# OSP_Carrier_V8_FM-ExG.net
KiCad netlist of a schematic drawn in Altium Designer
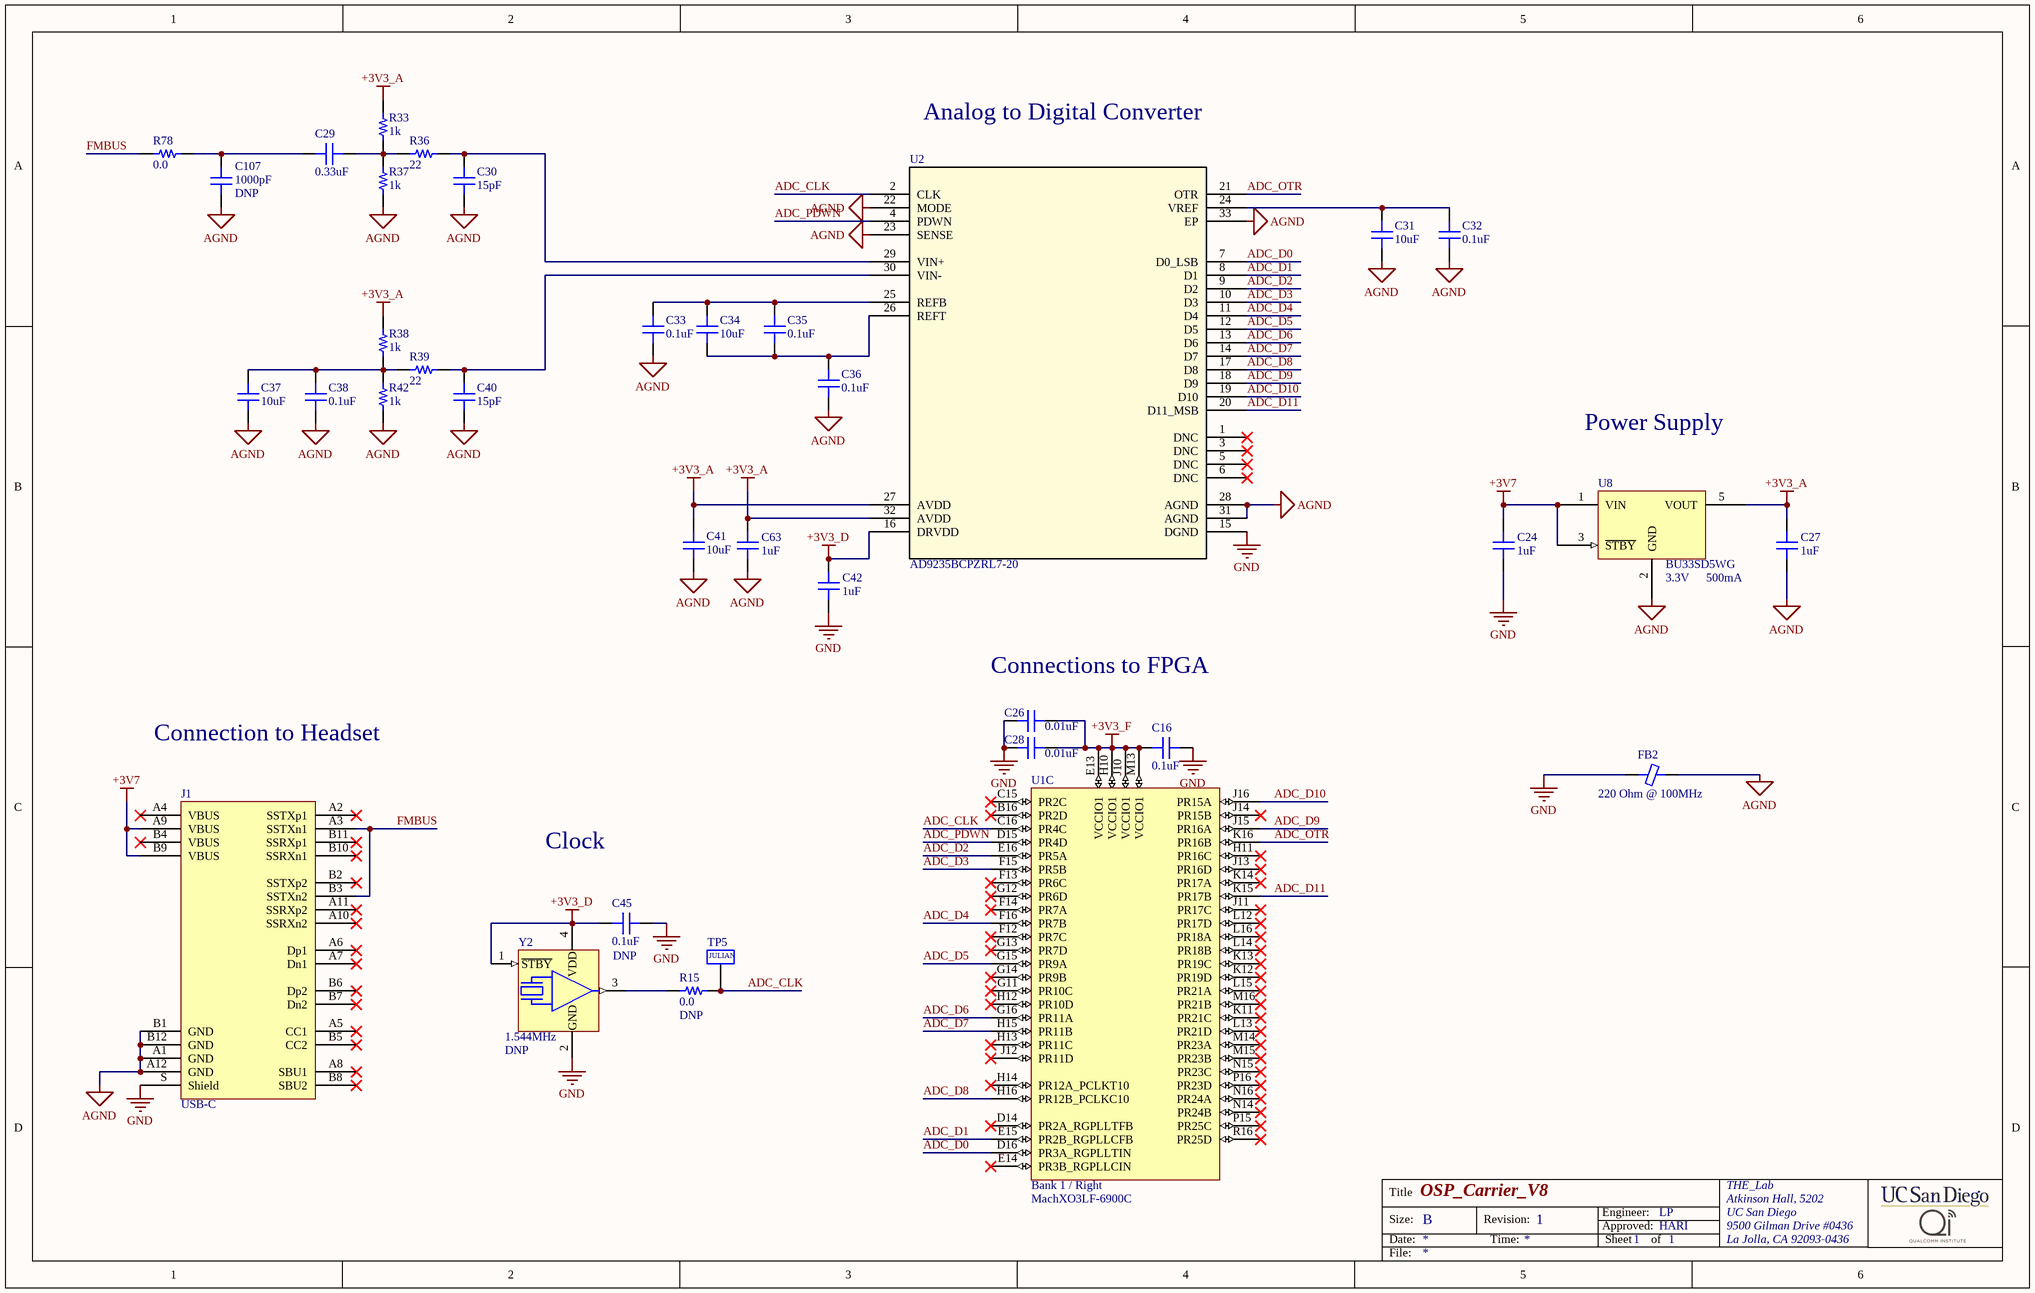
[diagram p0: OSP_Carrier_V8_FM-ExG.SchDoc]

(export (version "E")
  (design (tool "Eeschema 10.0.6"))
  (components
    (comp (ref "C16")
      (value "0.1uF")
      (footprint "CAP 0402/1005")
      (description "CAP CER 0.1UF 50V X7R 0402")
      (fields
        (field (name "PART NUMBER") "C1005X7R1H104K050BB")
        (field (name "MANUFACTURER") "TDK Corporation")
      )
      (libsource (lib "Celestial Library Database") (part "Capacitor"))
    )
    (comp (ref "C24")
      (value "1uF")
      (footprint "CAP 0402/1005")
      (description "CAP CER 1UF 10V X5R 0402")
      (fields
        (field (name "PART NUMBER") "GRM155R61A105KE15D")
        (field (name "MANUFACTURER") "Murata Electronics North America")
      )
      (libsource (lib "Celestial Library Database") (part "Capacitor"))
    )
    (comp (ref "C26")
      (value "0.01uF")
      (footprint "CAP 0402/1005")
      (description "CAP CER 10000PF 25V X7R 0402")
      (fields (field (name "PART NUMBER") "CC0402KRX7R8BB103") (field (name "MANUFACTURER") "Yageo"))
      (libsource (lib "Celestial Library Database") (part "Capacitor"))
    )
    (comp (ref "C27")
      (value "1uF")
      (footprint "CAP 0402/1005")
      (description "CAP CER 1UF 10V X5R 0402")
      (fields
        (field (name "PART NUMBER") "GRM155R61A105KE15D")
        (field (name "MANUFACTURER") "Murata Electronics North America")
      )
      (libsource (lib "Celestial Library Database") (part "Capacitor"))
    )
    (comp (ref "C28")
      (value "0.01uF")
      (footprint "CAP 0402/1005")
      (description "CAP CER 10000PF 25V X7R 0402")
      (fields (field (name "PART NUMBER") "CC0402KRX7R8BB103") (field (name "MANUFACTURER") "Yageo"))
      (libsource (lib "Celestial Library Database") (part "Capacitor"))
    )
    (comp (ref "C29")
      (value "0.33uF")
      (footprint "CAP 0402/1005")
      (description "CAP CER 1UF 10V X5R 0402")
      (fields
        (field (name "PART NUMBER") "GRM155R61A105KE15D")
        (field (name "MANUFACTURER") "Murata Electronics North America")
      )
      (libsource (lib "Celestial Library Database") (part "Capacitor"))
    )
    (comp (ref "C30")
      (value "15pF")
      (footprint "CAP 0402/1005")
      (description "CAP CER 15PF 50V C0G 0402")
      (fields
        (field (name "PART NUMBER") "C1005C0G1H150F050BA")
        (field (name "MANUFACTURER") "TDK Corporation")
      )
      (libsource (lib "Celestial Library Database") (part "Capacitor"))
    )
    (comp (ref "C31")
      (value "10uF")
      (footprint "CAP 0805/2012")
      (description "CAP CER 10UF 10V X5R 0805")
      (fields
        (field (name "PART NUMBER") "C2012X5R1A106M125AB")
        (field (name "MANUFACTURER") "TDK Corporation")
      )
      (libsource (lib "Celestial Library Database") (part "Capacitor"))
    )
    (comp (ref "C32")
      (value "0.1uF")
      (footprint "CAP 0402/1005")
      (description "CAP CER 0.1UF 50V X7R 0402")
      (fields
        (field (name "PART NUMBER") "C1005X7R1H104K050BB")
        (field (name "MANUFACTURER") "TDK Corporation")
      )
      (libsource (lib "Celestial Library Database") (part "Capacitor"))
    )
    (comp (ref "C33")
      (value "0.1uF")
      (footprint "CAP 0402/1005")
      (description "CAP CER 0.1UF 50V X7R 0402")
      (fields
        (field (name "PART NUMBER") "C1005X7R1H104K050BB")
        (field (name "MANUFACTURER") "TDK Corporation")
      )
      (libsource (lib "Celestial Library Database") (part "Capacitor"))
    )
    (comp (ref "C34")
      (value "10uF")
      (footprint "CAP 0805/2012")
      (description "CAP CER 10UF 10V X5R 0805")
      (fields
        (field (name "PART NUMBER") "C2012X5R1A106M125AB")
        (field (name "MANUFACTURER") "TDK Corporation")
      )
      (libsource (lib "Celestial Library Database") (part "Capacitor"))
    )
    (comp (ref "C35")
      (value "0.1uF")
      (footprint "CAP 0402/1005")
      (description "CAP CER 0.1UF 50V X7R 0402")
      (fields
        (field (name "PART NUMBER") "C1005X7R1H104K050BB")
        (field (name "MANUFACTURER") "TDK Corporation")
      )
      (libsource (lib "Celestial Library Database") (part "Capacitor"))
    )
    (comp (ref "C36")
      (value "0.1uF")
      (footprint "CAP 0402/1005")
      (description "CAP CER 0.1UF 50V X7R 0402")
      (fields
        (field (name "PART NUMBER") "C1005X7R1H104K050BB")
        (field (name "MANUFACTURER") "TDK Corporation")
      )
      (libsource (lib "Celestial Library Database") (part "Capacitor"))
    )
    (comp (ref "C37")
      (value "10uF")
      (footprint "CAP 0805/2012")
      (description "CAP CER 10UF 10V X5R 0805")
      (fields
        (field (name "PART NUMBER") "C2012X5R1A106M125AB")
        (field (name "MANUFACTURER") "TDK Corporation")
      )
      (libsource (lib "Celestial Library Database") (part "Capacitor"))
    )
    (comp (ref "C38")
      (value "0.1uF")
      (footprint "CAP 0402/1005")
      (description "CAP CER 0.1UF 50V X7R 0402")
      (fields
        (field (name "PART NUMBER") "C1005X7R1H104K050BB")
        (field (name "MANUFACTURER") "TDK Corporation")
      )
      (libsource (lib "Celestial Library Database") (part "Capacitor"))
    )
    (comp (ref "C40")
      (value "15pF")
      (footprint "CAP 0402/1005")
      (description "CAP CER 15PF 50V C0G 0402")
      (fields
        (field (name "PART NUMBER") "C1005C0G1H150F050BA")
        (field (name "MANUFACTURER") "TDK Corporation")
      )
      (libsource (lib "Celestial Library Database") (part "Capacitor"))
    )
    (comp (ref "C41")
      (value "10uF")
      (footprint "CAP 0805/2012")
      (description "CAP CER 10UF 10V X5R 0805")
      (fields
        (field (name "PART NUMBER") "C2012X5R1A106M125AB")
        (field (name "MANUFACTURER") "TDK Corporation")
      )
      (libsource (lib "Celestial Library Database") (part "Capacitor"))
    )
    (comp (ref "C42")
      (value "1uF")
      (footprint "CAP 0402/1005")
      (description "CAP CER 1UF 10V X5R 0402")
      (fields
        (field (name "PART NUMBER") "GRM155R61A105KE15D")
        (field (name "MANUFACTURER") "Murata Electronics North America")
      )
      (libsource (lib "Celestial Library Database") (part "Capacitor"))
    )
    (comp (ref "C45")
      (value "0.1uF")
      (footprint "CAP 0402/1005")
      (description "CAP CER 0.1UF 50V X7R 0402")
      (fields
        (field (name "PART NUMBER") "C1005X7R1H104K050BB")
        (field (name "MANUFACTURER") "TDK Corporation")
        (field (name "DNP") "DNP")
      )
      (libsource (lib "Celestial Library Database") (part "Capacitor"))
    )
    (comp (ref "C63")
      (value "1uF")
      (footprint "CAP 0402/1005")
      (description "CAP CER 1UF 10V X5R 0402")
      (fields
        (field (name "PART NUMBER") "GRM155R61A105KE15D")
        (field (name "MANUFACTURER") "Murata Electronics North America")
      )
      (libsource (lib "Celestial Library Database") (part "Capacitor"))
    )
    (comp (ref "C107")
      (value "1000pF")
      (footprint "CAP 0805/2012")
      (description "CAP CER 1000PF 50V C0G 0805")
      (fields
        (field (name "PART NUMBER") "C2012C0G1H102J060AA")
        (field (name "MANUFACTURER") "TDK Corporation")
        (field (name "DNP") "DNP")
      )
      (libsource (lib "Celestial Library Database") (part "Capacitor"))
    )
    (comp (ref "FB2")
      (value "220 Ohm @ 100MHz")
      (footprint "FER 0402/1005")
      (description "FERRITE CHIP 220 OHM 500MA 0402")
      (fields
        (field (name "PART NUMBER") "CIM05U221NC")
        (field (name "MANUFACTURER") "Samsung Electro-Mechanics America, Inc.")
      )
      (libsource (lib "Celestial Library Database") (part "Ferrite Chip"))
    )
    (comp (ref "J1")
      (value "USB-C")
      (footprint "TE_USB-C_2129691-1")
      (description "TE 2129691-1 USB-C Socket")
      (libsource (lib "OSP_Symbols") (part "TE_USB_C_2129691-1"))
    )
    (comp (ref "R15")
      (value "0.0")
      (footprint "RES 0603/1608")
      (description "RES SMD 0.0 OHM JUMPER 1/4W 0603")
      (fields
        (field (name "PART NUMBER") "CRCW06030000Z0EAHP")
        (field (name "MANUFACTURER") "Vishay Dale")
        (field (name "DNP") "DNP")
      )
      (libsource (lib "Celestial Library Database") (part "Resistor"))
    )
    (comp (ref "R33")
      (value "1k")
      (footprint "RES 0402/1005")
      (description "RES SMD 1K OHM 1% 1/10W 0402")
      (fields
        (field (name "PART NUMBER") "ERJ-2RKF1001X")
        (field (name "MANUFACTURER") "Panasonic Electronic Components")
      )
      (libsource (lib "Celestial Library Database") (part "Resistor"))
    )
    (comp (ref "R36")
      (value "22")
      (footprint "RES 0402/1005")
      (description "RES SMD 22 OHM 1% 1/10W 0402")
      (fields
        (field (name "PART NUMBER") "ERJ-2RKF22R0X")
        (field (name "MANUFACTURER") "Panasonic Electronic Components")
      )
      (libsource (lib "Celestial Library Database") (part "Resistor"))
    )
    (comp (ref "R37")
      (value "1k")
      (footprint "RES 0402/1005")
      (description "RES SMD 1K OHM 1% 1/10W 0402")
      (fields
        (field (name "PART NUMBER") "ERJ-2RKF1001X")
        (field (name "MANUFACTURER") "Panasonic Electronic Components")
      )
      (libsource (lib "Celestial Library Database") (part "Resistor"))
    )
    (comp (ref "R38")
      (value "1k")
      (footprint "RES 0402/1005")
      (description "RES SMD 1K OHM 1% 1/10W 0402")
      (fields
        (field (name "PART NUMBER") "ERJ-2RKF1001X")
        (field (name "MANUFACTURER") "Panasonic Electronic Components")
      )
      (libsource (lib "Celestial Library Database") (part "Resistor"))
    )
    (comp (ref "R39")
      (value "22")
      (footprint "RES 0402/1005")
      (description "RES SMD 22 OHM 1% 1/10W 0402")
      (fields
        (field (name "PART NUMBER") "ERJ-2RKF22R0X")
        (field (name "MANUFACTURER") "Panasonic Electronic Components")
      )
      (libsource (lib "Celestial Library Database") (part "Resistor"))
    )
    (comp (ref "R42")
      (value "1k")
      (footprint "RES 0402/1005")
      (description "RES SMD 1K OHM 1% 1/10W 0402")
      (fields
        (field (name "PART NUMBER") "ERJ-2RKF1001X")
        (field (name "MANUFACTURER") "Panasonic Electronic Components")
      )
      (libsource (lib "Celestial Library Database") (part "Resistor"))
    )
    (comp (ref "R78")
      (value "0.0")
      (footprint "RES 0805/2012")
      (description "RES SMD 0.0 OHM JUMPER 1/2W 0805")
      (fields (field (name "PART NUMBER") "CRCW08050000Z0EAHP") (field (name "MANUFACTURER") "Vishay Dale"))
      (libsource (lib "Celestial Library Database") (part "Resistor"))
    )
    (comp (ref "TP5")
      (value "TP_SMD_JULIAN")
      (footprint "TP_SMD_JULIAN")
      (description "Julian Extra-Large SMD Test Point")
      (libsource (lib "OSP_Symbols") (part "TP_SMD_JULIAN"))
    )
    (comp (ref "U1")
      (value "MachXO3LF-6900C")
      (footprint "LCMXO3_caBGA_BG256")
      (description "Lattice MachXO3LF-6900C-5BG256C FPGA")
      (libsource (lib "OSP_Symbols") (part "LCMXO3LF-6900C-XBG256X"))
    )
    (comp (ref "U2")
      (value "AD9235BCPZRL7-20")
      (footprint "CP_32_2-M")
      (description "Imported")
      (libsource (lib "AD9235BCPZRL7-20") (part "AD9235BCPZRL7-20"))
    )
    (comp (ref "U8")
      (value "BU33SD5WG")
      (footprint "ROHM_SSOP5")
      (description "ROHM BU33SD5WG-TR 3.3V 500mA LDO")
      (fields (field (name "VOLTAGE") "3.3V") (field (name "CURRENT") "500mA"))
      (libsource (lib "OSP_Symbols") (part "ROHM_BU33SD5WG"))
    )
    (comp (ref "Y2")
      (value "1.544MHz")
      (footprint "ABRACON_ASFLMB")
      (description "Abracon ASFLMB-1.544MHZ-LR-T")
      (fields (field (name "DNP") "DNP"))
      (libsource (lib "OSP_Symbols") (part "ABRA_ASFLMB-1.544MHZ-LR-T"))
    )
  )
  (nets
    (net (code "1") (name "+3V3_A") (class "Default")
      (node (ref "C27") (pin "1") (pinfunction "1_1") (pintype "passive"))
      (node (ref "C41") (pin "2") (pinfunction "2_2") (pintype "passive"))
      (node (ref "C63") (pin "1") (pinfunction "1_1") (pintype "passive"))
      (node (ref "R33") (pin "2") (pinfunction "2_2") (pintype "passive"))
      (node (ref "R38") (pin "2") (pinfunction "2_2") (pintype "passive"))
      (node (ref "U2") (pin "27") (pinfunction "AVDD_27") (pintype "power_in"))
      (node (ref "U2") (pin "32") (pinfunction "AVDD_32") (pintype "power_in"))
      (node (ref "U8") (pin "5") (pinfunction "VOUT_5") (pintype "power_in"))
    )
    (net (code "2") (name "+3V3_D") (class "Default")
      (node (ref "C42") (pin "1") (pinfunction "1_1") (pintype "passive"))
      (node (ref "C45") (pin "2") (pinfunction "2_2") (pintype "passive"))
      (node (ref "U2") (pin "16") (pinfunction "DRVDD_16") (pintype "power_in"))
      (node (ref "Y2") (pin "1") (pinfunction "~{STBY}_1") (pintype "input"))
      (node (ref "Y2") (pin "4") (pinfunction "VDD_4") (pintype "power_in"))
    )
    (net (code "3") (name "+3V3_F") (class "Default")
      (node (ref "C16") (pin "2") (pinfunction "2_2") (pintype "passive"))
      (node (ref "C26") (pin "1") (pinfunction "1_1") (pintype "passive"))
      (node (ref "C28") (pin "1") (pinfunction "1_1") (pintype "passive"))
      (node (ref "U1") (pin "E13") (pinfunction "VCCIO1_E13") (pintype "bidirectional"))
      (node (ref "U1") (pin "H10") (pinfunction "VCCIO1_H10") (pintype "bidirectional"))
      (node (ref "U1") (pin "J10") (pinfunction "VCCIO1_J10") (pintype "bidirectional"))
      (node (ref "U1") (pin "M13") (pinfunction "VCCIO1_M13") (pintype "bidirectional"))
    )
    (net (code "4") (name "+3V7") (class "Default")
      (node (ref "C24") (pin "1") (pinfunction "1_1") (pintype "passive"))
      (node (ref "J1") (pin "A9") (pinfunction "VBUS_A9") (pintype "passive"))
      (node (ref "J1") (pin "B9") (pinfunction "VBUS_B9") (pintype "passive"))
      (node (ref "U8") (pin "1") (pinfunction "VIN_1") (pintype "power_in"))
      (node (ref "U8") (pin "3") (pinfunction "~{STBY}_3") (pintype "input"))
    )
    (net (code "5") (name "/ADC_CLK") (class "Default")
      (node (ref "R15") (pin "1") (pinfunction "1_1") (pintype "passive"))
      (node (ref "TP5") (pin "1") (pintype "passive"))
      (node (ref "U1") (pin "C16") (pinfunction "PR4C_C16") (pintype "bidirectional"))
      (node (ref "U2") (pin "2") (pinfunction "CLK_2") (pintype "passive"))
    )
    (net (code "6") (name "/ADC_D0") (class "Default")
      (node (ref "U1") (pin "D16") (pinfunction "PR3A_RGPLLTIN_D16") (pintype "bidirectional"))
      (node (ref "U2") (pin "7") (pinfunction "D0_LSB_7") (pintype "passive"))
    )
    (net (code "7") (name "/ADC_D1") (class "Default")
      (node (ref "U1") (pin "E15") (pinfunction "PR2B_RGPLLCFB_E15") (pintype "bidirectional"))
      (node (ref "U2") (pin "8") (pinfunction "D1_8") (pintype "passive"))
    )
    (net (code "8") (name "/ADC_D2") (class "Default")
      (node (ref "U1") (pin "E16") (pinfunction "PR5A_E16") (pintype "bidirectional"))
      (node (ref "U2") (pin "9") (pinfunction "D2_9") (pintype "passive"))
    )
    (net (code "9") (name "/ADC_D3") (class "Default")
      (node (ref "U1") (pin "F15") (pinfunction "PR5B_F15") (pintype "bidirectional"))
      (node (ref "U2") (pin "10") (pinfunction "D3_10") (pintype "passive"))
    )
    (net (code "10") (name "/ADC_D4") (class "Default")
      (node (ref "U1") (pin "F16") (pinfunction "PR7B_F16") (pintype "bidirectional"))
      (node (ref "U2") (pin "11") (pinfunction "D4_11") (pintype "passive"))
    )
    (net (code "11") (name "/ADC_D5") (class "Default")
      (node (ref "U1") (pin "G15") (pinfunction "PR9A_G15") (pintype "bidirectional"))
      (node (ref "U2") (pin "12") (pinfunction "D5_12") (pintype "passive"))
    )
    (net (code "12") (name "/ADC_D6") (class "Default")
      (node (ref "U1") (pin "G16") (pinfunction "PR11A_G16") (pintype "bidirectional"))
      (node (ref "U2") (pin "13") (pinfunction "D6_13") (pintype "passive"))
    )
    (net (code "13") (name "/ADC_D7") (class "Default")
      (node (ref "U1") (pin "H15") (pinfunction "PR11B_H15") (pintype "bidirectional"))
      (node (ref "U2") (pin "14") (pinfunction "D7_14") (pintype "passive"))
    )
    (net (code "14") (name "/ADC_D8") (class "Default")
      (node (ref "U1") (pin "H16") (pinfunction "PR12B_PCLKC10_H16") (pintype "bidirectional"))
      (node (ref "U2") (pin "17") (pinfunction "D8_17") (pintype "passive"))
    )
    (net (code "15") (name "/ADC_D9") (class "Default")
      (node (ref "U1") (pin "J15") (pinfunction "PR16A_J15") (pintype "bidirectional"))
      (node (ref "U2") (pin "18") (pinfunction "D9_18") (pintype "passive"))
    )
    (net (code "16") (name "/ADC_D10") (class "Default")
      (node (ref "U1") (pin "J16") (pinfunction "PR15A_J16") (pintype "bidirectional"))
      (node (ref "U2") (pin "19") (pinfunction "D10_19") (pintype "passive"))
    )
    (net (code "17") (name "/ADC_D11") (class "Default")
      (node (ref "U1") (pin "K15") (pinfunction "PR17B_K15") (pintype "bidirectional"))
      (node (ref "U2") (pin "20") (pinfunction "D11_MSB_20") (pintype "passive"))
    )
    (net (code "18") (name "/ADC_OTR") (class "Default")
      (node (ref "U1") (pin "K16") (pinfunction "PR16B_K16") (pintype "bidirectional"))
      (node (ref "U2") (pin "21") (pinfunction "OTR_21") (pintype "passive"))
    )
    (net (code "19") (name "/ADC_PDWN") (class "Default")
      (node (ref "U1") (pin "D15") (pinfunction "PR4D_D15") (pintype "bidirectional"))
      (node (ref "U2") (pin "4") (pinfunction "PDWN_4") (pintype "passive"))
    )
    (net (code "20") (name "/FMBUS") (class "Default")
      (node (ref "J1") (pin "A3") (pinfunction "SSTXn1_A3") (pintype "passive"))
      (node (ref "J1") (pin "B3") (pinfunction "SSTXn2_B3") (pintype "passive"))
      (node (ref "R78") (pin "1") (pinfunction "1_1") (pintype "passive"))
    )
    (net (code "21") (name "AGND") (class "Default")
      (node (ref "C107") (pin "1") (pinfunction "1_1") (pintype "passive"))
      (node (ref "C27") (pin "2") (pinfunction "2_2") (pintype "passive"))
      (node (ref "C30") (pin "1") (pinfunction "1_1") (pintype "passive"))
      (node (ref "C31") (pin "1") (pinfunction "1_1") (pintype "passive"))
      (node (ref "C32") (pin "2") (pinfunction "2_2") (pintype "passive"))
      (node (ref "C33") (pin "2") (pinfunction "2_2") (pintype "passive"))
      (node (ref "C36") (pin "2") (pinfunction "2_2") (pintype "passive"))
      (node (ref "C37") (pin "1") (pinfunction "1_1") (pintype "passive"))
      (node (ref "C38") (pin "2") (pinfunction "2_2") (pintype "passive"))
      (node (ref "C40") (pin "1") (pinfunction "1_1") (pintype "passive"))
      (node (ref "C41") (pin "1") (pinfunction "1_1") (pintype "passive"))
      (node (ref "C63") (pin "2") (pinfunction "2_2") (pintype "passive"))
      (node (ref "FB2") (pin "2") (pinfunction "2_2") (pintype "passive"))
      (node (ref "J1") (pin "A1") (pinfunction "GND_A1") (pintype "passive"))
      (node (ref "J1") (pin "A12") (pinfunction "GND_A12") (pintype "passive"))
      (node (ref "J1") (pin "B1") (pinfunction "GND_B1") (pintype "passive"))
      (node (ref "J1") (pin "B12") (pinfunction "GND_B12") (pintype "passive"))
      (node (ref "R37") (pin "1") (pinfunction "1_1") (pintype "passive"))
      (node (ref "R42") (pin "1") (pinfunction "1_1") (pintype "passive"))
      (node (ref "U2") (pin "22") (pinfunction "MODE_22") (pintype "passive"))
      (node (ref "U2") (pin "23") (pinfunction "SENSE_23") (pintype "passive"))
      (node (ref "U2") (pin "28") (pinfunction "AGND_28") (pintype "passive"))
      (node (ref "U2") (pin "31") (pinfunction "AGND_31") (pintype "passive"))
      (node (ref "U2") (pin "33") (pinfunction "EP_33") (pintype "passive"))
      (node (ref "U8") (pin "2") (pinfunction "GND_2") (pintype "power_in"))
    )
    (net (code "22") (name "GND") (class "Default")
      (node (ref "C16") (pin "1") (pinfunction "1_1") (pintype "passive"))
      (node (ref "C24") (pin "2") (pinfunction "2_2") (pintype "passive"))
      (node (ref "C26") (pin "2") (pinfunction "2_2") (pintype "passive"))
      (node (ref "C28") (pin "2") (pinfunction "2_2") (pintype "passive"))
      (node (ref "C42") (pin "2") (pinfunction "2_2") (pintype "passive"))
      (node (ref "C45") (pin "1") (pinfunction "1_1") (pintype "passive"))
      (node (ref "FB2") (pin "1") (pinfunction "1_1") (pintype "passive"))
      (node (ref "J1") (pin "S") (pinfunction "Shield_S") (pintype "passive"))
      (node (ref "U2") (pin "15") (pinfunction "DGND_15") (pintype "passive"))
      (node (ref "Y2") (pin "2") (pinfunction "GND_2") (pintype "power_in"))
    )
    (net (code "23") (name "Net-(C29-Pad2)") (class "Default")
      (node (ref "C29") (pin "2") (pinfunction "2_2") (pintype "passive"))
      (node (ref "R33") (pin "1") (pinfunction "1_1") (pintype "passive"))
      (node (ref "R36") (pin "1") (pinfunction "1_1") (pintype "passive"))
      (node (ref "R37") (pin "2") (pinfunction "2_2") (pintype "passive"))
    )
    (net (code "24") (name "Net-(C37-Pad2)") (class "Default")
      (node (ref "C37") (pin "2") (pinfunction "2_2") (pintype "passive"))
      (node (ref "C38") (pin "1") (pinfunction "1_1") (pintype "passive"))
      (node (ref "R38") (pin "1") (pinfunction "1_1") (pintype "passive"))
      (node (ref "R39") (pin "1") (pinfunction "1_1") (pintype "passive"))
      (node (ref "R42") (pin "2") (pinfunction "2_2") (pintype "passive"))
    )
    (net (code "25") (name "Net-(C107-Pad2)") (class "Default")
      (node (ref "C107") (pin "2") (pinfunction "2_2") (pintype "passive"))
      (node (ref "C29") (pin "1") (pinfunction "1_1") (pintype "passive"))
      (node (ref "R78") (pin "2") (pinfunction "2_2") (pintype "passive"))
    )
    (net (code "26") (name "Net-(U2-REFB)") (class "Default")
      (node (ref "C33") (pin "1") (pinfunction "1_1") (pintype "passive"))
      (node (ref "C34") (pin "2") (pinfunction "2_2") (pintype "passive"))
      (node (ref "C35") (pin "1") (pinfunction "1_1") (pintype "passive"))
      (node (ref "U2") (pin "25") (pinfunction "REFB_25") (pintype "passive"))
    )
    (net (code "27") (name "Net-(U2-REFT)") (class "Default")
      (node (ref "C34") (pin "1") (pinfunction "1_1") (pintype "passive"))
      (node (ref "C35") (pin "2") (pinfunction "2_2") (pintype "passive"))
      (node (ref "C36") (pin "1") (pinfunction "1_1") (pintype "passive"))
      (node (ref "U2") (pin "26") (pinfunction "REFT_26") (pintype "passive"))
    )
    (net (code "28") (name "Net-(U2-VIN+)") (class "Default")
      (node (ref "C30") (pin "2") (pinfunction "2_2") (pintype "passive"))
      (node (ref "R36") (pin "2") (pinfunction "2_2") (pintype "passive"))
      (node (ref "U2") (pin "29") (pinfunction "VIN+_29") (pintype "passive"))
    )
    (net (code "29") (name "Net-(U2-VIN-)") (class "Default")
      (node (ref "C40") (pin "2") (pinfunction "2_2") (pintype "passive"))
      (node (ref "R39") (pin "2") (pinfunction "2_2") (pintype "passive"))
      (node (ref "U2") (pin "30") (pinfunction "VIN-_30") (pintype "passive"))
    )
    (net (code "30") (name "Net-(U2-VREF)") (class "Default")
      (node (ref "C31") (pin "2") (pinfunction "2_2") (pintype "passive"))
      (node (ref "C32") (pin "1") (pinfunction "1_1") (pintype "passive"))
      (node (ref "U2") (pin "24") (pinfunction "VREF_24") (pintype "passive"))
    )
    (net (code "31") (name "Net-(Y2-OUT)") (class "Default")
      (node (ref "R15") (pin "2") (pinfunction "2_2") (pintype "passive"))
      (node (ref "Y2") (pin "3") (pinfunction "OUT_3") (pintype "output"))
    )
    (net (code "32") (name "unconnected-(J1-CC1-PadA5)") (class "Default")
      (node (ref "J1") (pin "A5") (pinfunction "CC1_A5") (pintype "passive+no_connect"))
    )
    (net (code "33") (name "unconnected-(J1-CC2-PadB5)") (class "Default")
      (node (ref "J1") (pin "B5") (pinfunction "CC2_B5") (pintype "passive+no_connect"))
    )
    (net (code "34") (name "unconnected-(J1-Dn1-PadA7)") (class "Default")
      (node (ref "J1") (pin "A7") (pinfunction "Dn1_A7") (pintype "passive+no_connect"))
    )
    (net (code "35") (name "unconnected-(J1-Dn2-PadB7)") (class "Default")
      (node (ref "J1") (pin "B7") (pinfunction "Dn2_B7") (pintype "passive+no_connect"))
    )
    (net (code "36") (name "unconnected-(J1-Dp1-PadA6)") (class "Default")
      (node (ref "J1") (pin "A6") (pinfunction "Dp1_A6") (pintype "passive+no_connect"))
    )
    (net (code "37") (name "unconnected-(J1-Dp2-PadB6)") (class "Default")
      (node (ref "J1") (pin "B6") (pinfunction "Dp2_B6") (pintype "passive+no_connect"))
    )
    (net (code "38") (name "unconnected-(J1-SBU1-PadA8)") (class "Default")
      (node (ref "J1") (pin "A8") (pinfunction "SBU1_A8") (pintype "passive+no_connect"))
    )
    (net (code "39") (name "unconnected-(J1-SBU2-PadB8)") (class "Default")
      (node (ref "J1") (pin "B8") (pinfunction "SBU2_B8") (pintype "passive+no_connect"))
    )
    (net (code "40") (name "unconnected-(J1-SSRXn1-PadB10)") (class "Default")
      (node (ref "J1") (pin "B10") (pinfunction "SSRXn1_B10") (pintype "passive+no_connect"))
    )
    (net (code "41") (name "unconnected-(J1-SSRXn2-PadA10)") (class "Default")
      (node (ref "J1") (pin "A10") (pinfunction "SSRXn2_A10") (pintype "passive+no_connect"))
    )
    (net (code "42") (name "unconnected-(J1-SSRXp1-PadB11)") (class "Default")
      (node (ref "J1") (pin "B11") (pinfunction "SSRXp1_B11") (pintype "passive+no_connect"))
    )
    (net (code "43") (name "unconnected-(J1-SSRXp2-PadA11)") (class "Default")
      (node (ref "J1") (pin "A11") (pinfunction "SSRXp2_A11") (pintype "passive+no_connect"))
    )
    (net (code "44") (name "unconnected-(J1-SSTXp1-PadA2)") (class "Default")
      (node (ref "J1") (pin "A2") (pinfunction "SSTXp1_A2") (pintype "passive+no_connect"))
    )
    (net (code "45") (name "unconnected-(J1-SSTXp2-PadB2)") (class "Default")
      (node (ref "J1") (pin "B2") (pinfunction "SSTXp2_B2") (pintype "passive+no_connect"))
    )
    (net (code "46") (name "unconnected-(J1-VBUS-PadA4)") (class "Default")
      (node (ref "J1") (pin "A4") (pinfunction "VBUS_A4") (pintype "passive+no_connect"))
    )
    (net (code "47") (name "unconnected-(J1-VBUS-PadB4)") (class "Default")
      (node (ref "J1") (pin "B4") (pinfunction "VBUS_B4") (pintype "passive+no_connect"))
    )
    (net (code "48") (name "unconnected-(U1C-PR2A_RGPLLTFB-PadD14)") (class "Default")
      (node (ref "U1") (pin "D14") (pinfunction "PR2A_RGPLLTFB_D14") (pintype "bidirectional+no_connect"))
    )
    (net (code "49") (name "unconnected-(U1C-PR2C-PadC15)") (class "Default")
      (node (ref "U1") (pin "C15") (pinfunction "PR2C_C15") (pintype "bidirectional+no_connect"))
    )
    (net (code "50") (name "unconnected-(U1C-PR2D-PadB16)") (class "Default")
      (node (ref "U1") (pin "B16") (pinfunction "PR2D_B16") (pintype "bidirectional+no_connect"))
    )
    (net (code "51") (name "unconnected-(U1C-PR3B_RGPLLCIN-PadE14)") (class "Default")
      (node (ref "U1") (pin "E14") (pinfunction "PR3B_RGPLLCIN_E14") (pintype "bidirectional+no_connect"))
    )
    (net (code "52") (name "unconnected-(U1C-PR6C-PadF13)") (class "Default")
      (node (ref "U1") (pin "F13") (pinfunction "PR6C_F13") (pintype "bidirectional+no_connect"))
    )
    (net (code "53") (name "unconnected-(U1C-PR6D-PadG12)") (class "Default")
      (node (ref "U1") (pin "G12") (pinfunction "PR6D_G12") (pintype "bidirectional+no_connect"))
    )
    (net (code "54") (name "unconnected-(U1C-PR7A-PadF14)") (class "Default")
      (node (ref "U1") (pin "F14") (pinfunction "PR7A_F14") (pintype "bidirectional+no_connect"))
    )
    (net (code "55") (name "unconnected-(U1C-PR7C-PadF12)") (class "Default")
      (node (ref "U1") (pin "F12") (pinfunction "PR7C_F12") (pintype "bidirectional+no_connect"))
    )
    (net (code "56") (name "unconnected-(U1C-PR7D-PadG13)") (class "Default")
      (node (ref "U1") (pin "G13") (pinfunction "PR7D_G13") (pintype "bidirectional+no_connect"))
    )
    (net (code "57") (name "unconnected-(U1C-PR9B-PadG14)") (class "Default")
      (node (ref "U1") (pin "G14") (pinfunction "PR9B_G14") (pintype "bidirectional+no_connect"))
    )
    (net (code "58") (name "unconnected-(U1C-PR10C-PadG11)") (class "Default")
      (node (ref "U1") (pin "G11") (pinfunction "PR10C_G11") (pintype "bidirectional+no_connect"))
    )
    (net (code "59") (name "unconnected-(U1C-PR10D-PadH12)") (class "Default")
      (node (ref "U1") (pin "H12") (pinfunction "PR10D_H12") (pintype "bidirectional+no_connect"))
    )
    (net (code "60") (name "unconnected-(U1C-PR11C-PadH13)") (class "Default")
      (node (ref "U1") (pin "H13") (pinfunction "PR11C_H13") (pintype "bidirectional+no_connect"))
    )
    (net (code "61") (name "unconnected-(U1C-PR11D-PadJ12)") (class "Default")
      (node (ref "U1") (pin "J12") (pinfunction "PR11D_J12") (pintype "bidirectional+no_connect"))
    )
    (net (code "62") (name "unconnected-(U1C-PR12A_PCLKT10-PadH14)") (class "Default")
      (node (ref "U1") (pin "H14") (pinfunction "PR12A_PCLKT10_H14") (pintype "bidirectional+no_connect"))
    )
    (net (code "63") (name "unconnected-(U1C-PR15B-PadJ14)") (class "Default")
      (node (ref "U1") (pin "J14") (pinfunction "PR15B_J14") (pintype "bidirectional+no_connect"))
    )
    (net (code "64") (name "unconnected-(U1C-PR16C-PadH11)") (class "Default")
      (node (ref "U1") (pin "H11") (pinfunction "PR16C_H11") (pintype "bidirectional+no_connect"))
    )
    (net (code "65") (name "unconnected-(U1C-PR16D-PadJ13)") (class "Default")
      (node (ref "U1") (pin "J13") (pinfunction "PR16D_J13") (pintype "bidirectional+no_connect"))
    )
    (net (code "66") (name "unconnected-(U1C-PR17A-PadK14)") (class "Default")
      (node (ref "U1") (pin "K14") (pinfunction "PR17A_K14") (pintype "bidirectional+no_connect"))
    )
    (net (code "67") (name "unconnected-(U1C-PR17C-PadJ11)") (class "Default")
      (node (ref "U1") (pin "J11") (pinfunction "PR17C_J11") (pintype "bidirectional+no_connect"))
    )
    (net (code "68") (name "unconnected-(U1C-PR17D-PadL12)") (class "Default")
      (node (ref "U1") (pin "L12") (pinfunction "PR17D_L12") (pintype "bidirectional+no_connect"))
    )
    (net (code "69") (name "unconnected-(U1C-PR18A-PadL16)") (class "Default")
      (node (ref "U1") (pin "L16") (pinfunction "PR18A_L16") (pintype "bidirectional+no_connect"))
    )
    (net (code "70") (name "unconnected-(U1C-PR18B-PadL14)") (class "Default")
      (node (ref "U1") (pin "L14") (pinfunction "PR18B_L14") (pintype "bidirectional+no_connect"))
    )
    (net (code "71") (name "unconnected-(U1C-PR19C-PadK13)") (class "Default")
      (node (ref "U1") (pin "K13") (pinfunction "PR19C_K13") (pintype "bidirectional+no_connect"))
    )
    (net (code "72") (name "unconnected-(U1C-PR19D-PadK12)") (class "Default")
      (node (ref "U1") (pin "K12") (pinfunction "PR19D_K12") (pintype "bidirectional+no_connect"))
    )
    (net (code "73") (name "unconnected-(U1C-PR21A-PadL15)") (class "Default")
      (node (ref "U1") (pin "L15") (pinfunction "PR21A_L15") (pintype "bidirectional+no_connect"))
    )
    (net (code "74") (name "unconnected-(U1C-PR21B-PadM16)") (class "Default")
      (node (ref "U1") (pin "M16") (pinfunction "PR21B_M16") (pintype "bidirectional+no_connect"))
    )
    (net (code "75") (name "unconnected-(U1C-PR21C-PadK11)") (class "Default")
      (node (ref "U1") (pin "K11") (pinfunction "PR21C_K11") (pintype "bidirectional+no_connect"))
    )
    (net (code "76") (name "unconnected-(U1C-PR21D-PadL13)") (class "Default")
      (node (ref "U1") (pin "L13") (pinfunction "PR21D_L13") (pintype "bidirectional+no_connect"))
    )
    (net (code "77") (name "unconnected-(U1C-PR23A-PadM14)") (class "Default")
      (node (ref "U1") (pin "M14") (pinfunction "PR23A_M14") (pintype "bidirectional+no_connect"))
    )
    (net (code "78") (name "unconnected-(U1C-PR23B-PadM15)") (class "Default")
      (node (ref "U1") (pin "M15") (pinfunction "PR23B_M15") (pintype "bidirectional+no_connect"))
    )
    (net (code "79") (name "unconnected-(U1C-PR23C-PadN15)") (class "Default")
      (node (ref "U1") (pin "N15") (pinfunction "PR23C_N15") (pintype "bidirectional+no_connect"))
    )
    (net (code "80") (name "unconnected-(U1C-PR23D-PadP16)") (class "Default")
      (node (ref "U1") (pin "P16") (pinfunction "PR23D_P16") (pintype "bidirectional+no_connect"))
    )
    (net (code "81") (name "unconnected-(U1C-PR24A-PadN16)") (class "Default")
      (node (ref "U1") (pin "N16") (pinfunction "PR24A_N16") (pintype "bidirectional+no_connect"))
    )
    (net (code "82") (name "unconnected-(U1C-PR24B-PadN14)") (class "Default")
      (node (ref "U1") (pin "N14") (pinfunction "PR24B_N14") (pintype "bidirectional+no_connect"))
    )
    (net (code "83") (name "unconnected-(U1C-PR25C-PadP15)") (class "Default")
      (node (ref "U1") (pin "P15") (pinfunction "PR25C_P15") (pintype "bidirectional+no_connect"))
    )
    (net (code "84") (name "unconnected-(U1C-PR25D-PadR16)") (class "Default")
      (node (ref "U1") (pin "R16") (pinfunction "PR25D_R16") (pintype "bidirectional+no_connect"))
    )
    (net (code "85") (name "unconnected-(U2-DNC-Pad1)") (class "Default")
      (node (ref "U2") (pin "1") (pinfunction "DNC_1") (pintype "passive+no_connect"))
    )
    (net (code "86") (name "unconnected-(U2-DNC-Pad3)") (class "Default")
      (node (ref "U2") (pin "3") (pinfunction "DNC_3") (pintype "passive+no_connect"))
    )
    (net (code "87") (name "unconnected-(U2-DNC-Pad5)") (class "Default")
      (node (ref "U2") (pin "5") (pinfunction "DNC_5") (pintype "passive+no_connect"))
    )
    (net (code "88") (name "unconnected-(U2-DNC-Pad6)") (class "Default")
      (node (ref "U2") (pin "6") (pinfunction "DNC_6") (pintype "passive+no_connect"))
    )
  )
)
